# imu_sense.net
KiCad netlist of a schematic drawn in Altium Designer
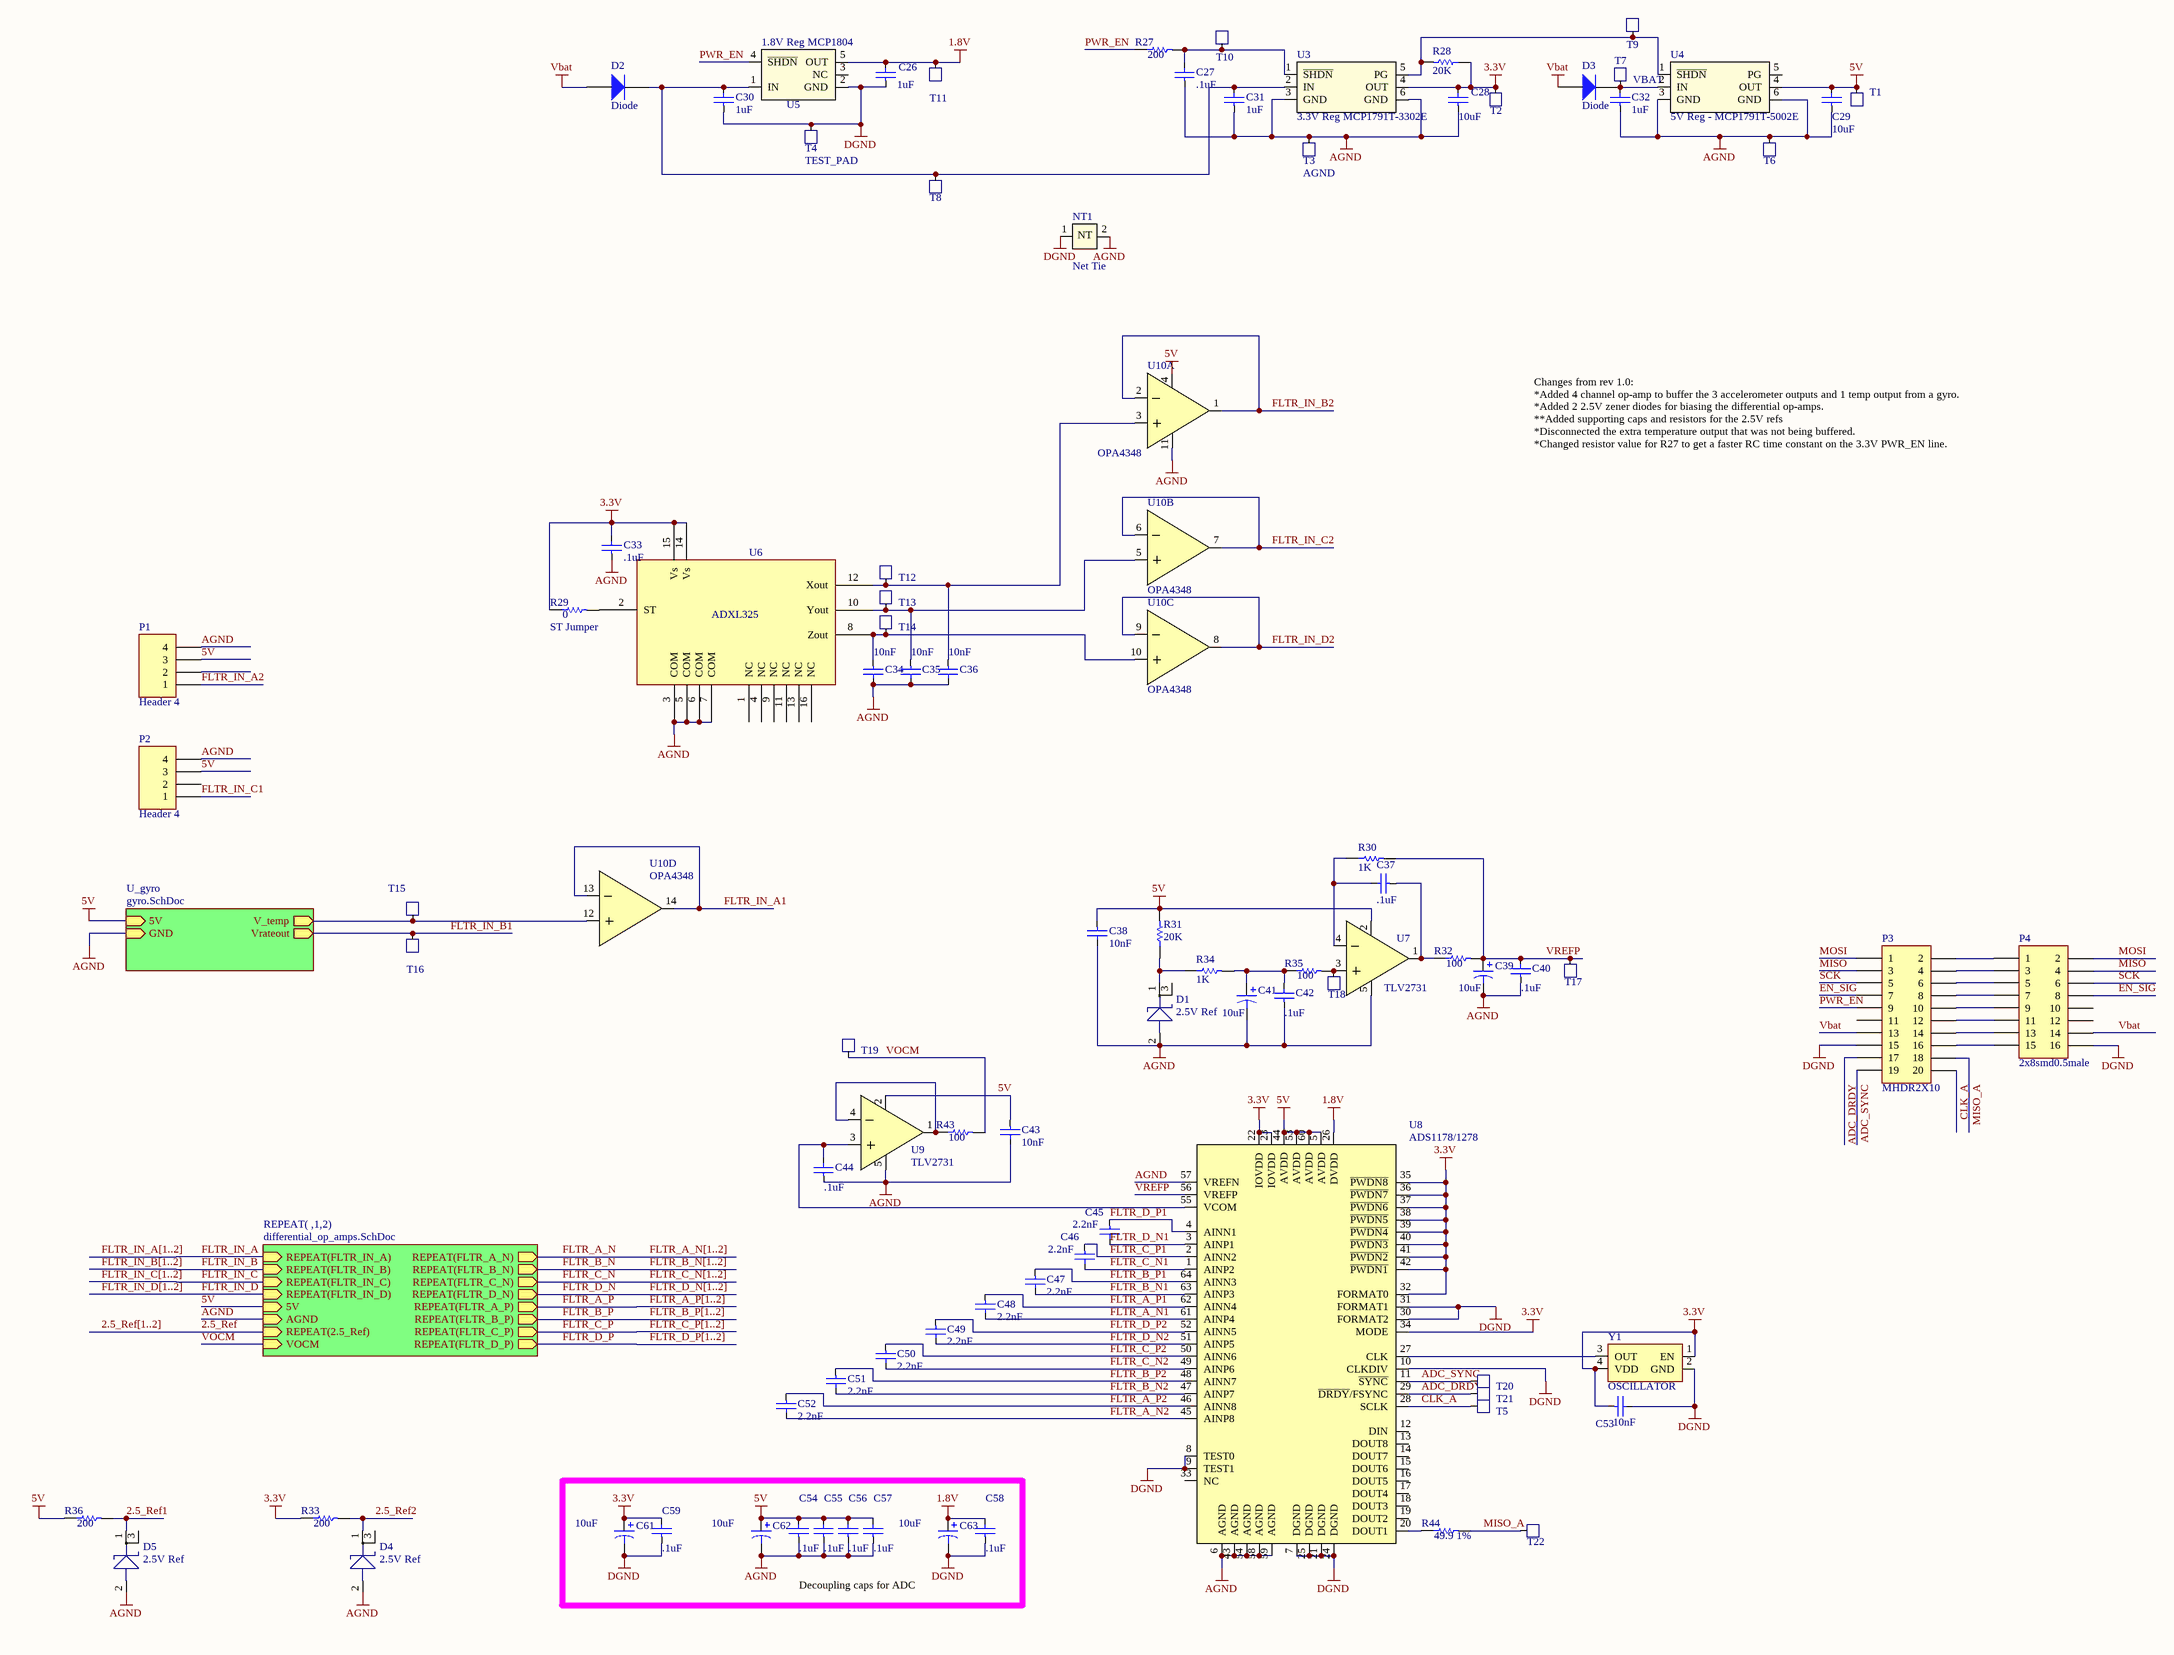
[diagram p0: imu_sense.SchDoc]

(export (version "E")
  (design (tool "Eeschema 10.0.6"))
  (components
    (comp (ref "C26")
      (value "1uF")
      (footprint "0603 (1608)")
      (fields
        (field (name "MANUFACTURER") "Murata")
        (field (name "PART NO.") "81-GRM188R61E105KA12")
        (field (name "TOLERANCE") "10%")
      )
      (libsource (lib "SMT Chip") (part "Capacitor"))
    )
    (comp (ref "C27")
      (value ".1uF")
      (footprint "0603 (1608)")
      (fields
        (field (name "MANUFACTURER") "Murata")
        (field (name "PART NO.") "490-1524-1-ND")
        (field (name "Comment") "Capacitor")
      )
      (libsource (lib "SMT Chip") (part "Capacitor"))
    )
    (comp (ref "C28")
      (value "10uF")
      (footprint "0603 (1608)")
      (fields
        (field (name "MANUFACTURER") "Murata")
        (field (name "PART NO.") "810-C1608X5R0J106K")
        (field (name "TOLERANCE") "10%")
      )
      (libsource (lib "SMT Chip") (part "Capacitor"))
    )
    (comp (ref "C29")
      (value "10uF")
      (footprint "0603 (1608)")
      (fields
        (field (name "MANUFACTURER") "Murata")
        (field (name "PART NO.") "810-C1608X5R0J106K")
        (field (name "TOLERANCE") "10%")
      )
      (libsource (lib "SMT Chip") (part "Capacitor"))
    )
    (comp (ref "C30")
      (value "1uF")
      (footprint "0603 (1608)")
      (fields
        (field (name "MANUFACTURER") "Murata")
        (field (name "PART NO.") "81-GRM188R61E105KA12")
        (field (name "TOLERANCE") "10%")
      )
      (libsource (lib "SMT Chip") (part "Capacitor"))
    )
    (comp (ref "C31")
      (value "1uF")
      (footprint "0603 (1608)")
      (fields
        (field (name "MANUFACTURER") "Murata")
        (field (name "PART NO.") "81-GRM188R61E105KA12")
        (field (name "TOLERANCE") "10%")
      )
      (libsource (lib "SMT Chip") (part "Capacitor"))
    )
    (comp (ref "C32")
      (value "1uF")
      (footprint "0603 (1608)")
      (fields
        (field (name "MANUFACTURER") "Murata")
        (field (name "PART NO.") "81-GRM188R61E105KA12")
        (field (name "TOLERANCE") "10%")
      )
      (libsource (lib "SMT Chip") (part "Capacitor"))
    )
    (comp (ref "C33")
      (value ".1uF")
      (footprint "0603 (1608)")
      (fields
        (field (name "MANUFACTURER") "Murata")
        (field (name "PART NO.") "490-1524-1-ND")
        (field (name "Comment") "Capacitor")
      )
      (libsource (lib "SMT Chip") (part "Capacitor"))
    )
    (comp (ref "C34")
      (value "10nF")
      (footprint "0603 (1608)")
      (fields
        (field (name "MANUFACTURER") "TDK")
        (field (name "PART NO.") "445-5099-1-ND")
        (field (name "TOLERANCE") "5%")
      )
      (libsource (lib "SMT Chip") (part "Capacitor"))
    )
    (comp (ref "C35")
      (value "10nF")
      (footprint "0603 (1608)")
      (fields
        (field (name "MANUFACTURER") "TDK")
        (field (name "PART NO.") "445-5099-1-ND")
        (field (name "TOLERANCE") "5%")
      )
      (libsource (lib "SMT Chip") (part "Capacitor"))
    )
    (comp (ref "C36")
      (value "10nF")
      (footprint "0603 (1608)")
      (fields
        (field (name "MANUFACTURER") "TDK")
        (field (name "PART NO.") "445-5099-1-ND")
        (field (name "TOLERANCE") "5%")
      )
      (libsource (lib "SMT Chip") (part "Capacitor"))
    )
    (comp (ref "C37")
      (value ".1uF")
      (footprint "0603 (1608)")
      (fields
        (field (name "MANUFACTURER") "Murata")
        (field (name "PART NO.") "490-1524-1-ND")
        (field (name "Comment") "Capacitor")
      )
      (libsource (lib "SMT Chip") (part "Capacitor"))
    )
    (comp (ref "C38")
      (value "10nF")
      (footprint "0603 (1608)")
      (fields
        (field (name "MANUFACTURER") "TDK")
        (field (name "PART NO.") "445-5099-1-ND")
        (field (name "TOLERANCE") "5%")
      )
      (libsource (lib "SMT Chip") (part "Capacitor"))
    )
    (comp (ref "C39")
      (value "10uF")
      (footprint "CAP-POL 0603(1608)")
      (description "Polarized Capacitor (Surface Mount)")
      (fields (field (name "PART NO.") "71-298D106X06R3M2T") (field (name "Comment") "tant"))
      (libsource (lib "Miscellaneous Devices") (part "Cap Pol3"))
    )
    (comp (ref "C40")
      (value ".1uF")
      (footprint "0603 (1608)")
      (fields
        (field (name "MANUFACTURER") "Murata")
        (field (name "PART NO.") "490-1524-1-ND")
        (field (name "Comment") "Capacitor")
      )
      (libsource (lib "SMT Chip") (part "Capacitor"))
    )
    (comp (ref "C41")
      (value "10uF")
      (footprint "CAP-POL 0603(1608)")
      (description "Polarized Capacitor (Surface Mount)")
      (fields (field (name "PART NO.") "71-298D106X06R3M2T") (field (name "Comment") "tant"))
      (libsource (lib "Miscellaneous Devices") (part "Cap Pol3"))
    )
    (comp (ref "C42")
      (value ".1uF")
      (footprint "0603 (1608)")
      (fields
        (field (name "MANUFACTURER") "Murata")
        (field (name "PART NO.") "490-1524-1-ND")
        (field (name "Comment") "Capacitor")
      )
      (libsource (lib "SMT Chip") (part "Capacitor"))
    )
    (comp (ref "C43")
      (value "10nF")
      (footprint "0603 (1608)")
      (fields
        (field (name "MANUFACTURER") "TDK")
        (field (name "PART NO.") "445-5099-1-ND")
        (field (name "TOLERANCE") "5%")
      )
      (libsource (lib "SMT Chip") (part "Capacitor"))
    )
    (comp (ref "C44")
      (value ".1uF")
      (footprint "0603 (1608)")
      (fields
        (field (name "MANUFACTURER") "Murata")
        (field (name "PART NO.") "490-1524-1-ND")
        (field (name "Comment") "Capacitor")
      )
      (libsource (lib "SMT Chip") (part "Capacitor"))
    )
    (comp (ref "C45")
      (value "2.2nF")
      (footprint "0603 (1608)")
      (description "COG Ceramic Cap -> near input to ads1178")
      (fields (field (name "MANUFACTURER") "Murata") (field (name "PART NO.") "490-1459-1-ND"))
      (libsource (lib "SMT Chip") (part "Capacitor"))
    )
    (comp (ref "C46")
      (value "2.2nF")
      (footprint "0603 (1608)")
      (description "COG Ceramic Cap -> near input to ads1178")
      (fields (field (name "MANUFACTURER") "Murata") (field (name "PART NO.") "490-1459-1-ND"))
      (libsource (lib "SMT Chip") (part "Capacitor"))
    )
    (comp (ref "C47")
      (value "2.2nF")
      (footprint "0603 (1608)")
      (description "COG Ceramic Cap -> near input to ads1178")
      (fields (field (name "MANUFACTURER") "Murata") (field (name "PART NO.") "490-1459-1-ND"))
      (libsource (lib "SMT Chip") (part "Capacitor"))
    )
    (comp (ref "C48")
      (value "2.2nF")
      (footprint "0603 (1608)")
      (description "COG Ceramic Cap -> near input to ads1178")
      (fields (field (name "MANUFACTURER") "Murata") (field (name "PART NO.") "490-1459-1-ND"))
      (libsource (lib "SMT Chip") (part "Capacitor"))
    )
    (comp (ref "C49")
      (value "2.2nF")
      (footprint "0603 (1608)")
      (description "COG Ceramic Cap -> near input to ads1178")
      (fields (field (name "MANUFACTURER") "Murata") (field (name "PART NO.") "490-1459-1-ND"))
      (libsource (lib "SMT Chip") (part "Capacitor"))
    )
    (comp (ref "C50")
      (value "2.2nF")
      (footprint "0603 (1608)")
      (description "COG Ceramic Cap -> near input to ads1178")
      (fields (field (name "MANUFACTURER") "Murata") (field (name "PART NO.") "490-1459-1-ND"))
      (libsource (lib "SMT Chip") (part "Capacitor"))
    )
    (comp (ref "C51")
      (value "2.2nF")
      (footprint "0603 (1608)")
      (description "COG Ceramic Cap -> near input to ads1178")
      (fields (field (name "MANUFACTURER") "Murata") (field (name "PART NO.") "490-1459-1-ND"))
      (libsource (lib "SMT Chip") (part "Capacitor"))
    )
    (comp (ref "C52")
      (value "2.2nF")
      (footprint "0603 (1608)")
      (description "COG Ceramic Cap -> near input to ads1178")
      (fields (field (name "MANUFACTURER") "Murata") (field (name "PART NO.") "490-1459-1-ND"))
      (libsource (lib "SMT Chip") (part "Capacitor"))
    )
    (comp (ref "C53")
      (value "10nF")
      (footprint "0603 (1608)")
      (fields
        (field (name "MANUFACTURER") "TDK")
        (field (name "PART NO.") "445-5099-1-ND")
        (field (name "TOLERANCE") "5%")
      )
      (libsource (lib "SMT Chip") (part "Capacitor"))
    )
    (comp (ref "C54")
      (value ".1uF")
      (footprint "0603 (1608)")
      (fields
        (field (name "MANUFACTURER") "Murata")
        (field (name "PART NO.") "490-1524-1-ND")
        (field (name "Comment") "Capacitor")
      )
      (libsource (lib "SMT Chip") (part "Capacitor"))
    )
    (comp (ref "C55")
      (value ".1uF")
      (footprint "0603 (1608)")
      (fields
        (field (name "MANUFACTURER") "Murata")
        (field (name "PART NO.") "490-1524-1-ND")
        (field (name "Comment") "Capacitor")
      )
      (libsource (lib "SMT Chip") (part "Capacitor"))
    )
    (comp (ref "C56")
      (value ".1uF")
      (footprint "0603 (1608)")
      (fields
        (field (name "MANUFACTURER") "Murata")
        (field (name "PART NO.") "490-1524-1-ND")
        (field (name "Comment") "Capacitor")
      )
      (libsource (lib "SMT Chip") (part "Capacitor"))
    )
    (comp (ref "C57")
      (value ".1uF")
      (footprint "0603 (1608)")
      (fields
        (field (name "MANUFACTURER") "Murata")
        (field (name "PART NO.") "490-1524-1-ND")
        (field (name "Comment") "Capacitor")
      )
      (libsource (lib "SMT Chip") (part "Capacitor"))
    )
    (comp (ref "C58")
      (value ".1uF")
      (footprint "0603 (1608)")
      (fields
        (field (name "MANUFACTURER") "Murata")
        (field (name "PART NO.") "490-1524-1-ND")
        (field (name "Comment") "Capacitor")
      )
      (libsource (lib "SMT Chip") (part "Capacitor"))
    )
    (comp (ref "C59")
      (value ".1uF")
      (footprint "0603 (1608)")
      (fields
        (field (name "MANUFACTURER") "Murata")
        (field (name "PART NO.") "490-1524-1-ND")
        (field (name "Comment") "Capacitor")
      )
      (libsource (lib "SMT Chip") (part "Capacitor"))
    )
    (comp (ref "C61")
      (value "10uF")
      (footprint "CAP-POL 0603(1608)")
      (description "Polarized Capacitor (Surface Mount)")
      (fields (field (name "PART NO.") "71-298D106X06R3M2T") (field (name "Comment") "tant"))
      (libsource (lib "Miscellaneous Devices") (part "Cap Pol3"))
    )
    (comp (ref "C62")
      (value "10uF")
      (footprint "CAP-POL 0603(1608)")
      (description "Polarized Capacitor (Surface Mount)")
      (fields (field (name "PART NO.") "71-298D106X06R3M2T") (field (name "Comment") "tant"))
      (libsource (lib "Miscellaneous Devices") (part "Cap Pol3"))
    )
    (comp (ref "C63")
      (value "10uF")
      (footprint "CAP-POL 0603(1608)")
      (description "Polarized Capacitor (Surface Mount)")
      (fields (field (name "PART NO.") "71-298D106X06R3M2T") (field (name "Comment") "tant"))
      (libsource (lib "Miscellaneous Devices") (part "Cap Pol3"))
    )
    (comp (ref "D1")
      (value "2.5V Ref")
      (footprint "SC-70")
      (description "2.5 volt ref")
      (fields
        (field (name "PART NO.") "ADR525BKSZ-REEL7CT-ND")
        (field (name "MANUFACTURER") "Analog Devices")
      )
      (libsource (lib "imu") (part "ZENER"))
    )
    (comp (ref "D2")
      (value "Diode")
      (footprint "0603(1608) diode - line on pin2")
      (description "Reverse voltage protection diode")
      (fields (field (name "PART NO.") "641-1332-1-ND"))
      (libsource (lib "Miscellaneous Devices") (part "Diode"))
    )
    (comp (ref "D3")
      (value "Diode")
      (footprint "0603(1608) diode - line on pin2")
      (description "Reverse voltage protection diode")
      (fields (field (name "PART NO.") "641-1332-1-ND"))
      (libsource (lib "Miscellaneous Devices") (part "Diode"))
    )
    (comp (ref "D4")
      (value "2.5V Ref")
      (footprint "SC-70")
      (description "2.5 volt ref")
      (fields
        (field (name "PART NO.") "ADR525BKSZ-REEL7CT-ND")
        (field (name "MANUFACTURER") "Analog Devices")
      )
      (libsource (lib "imu") (part "ZENER"))
    )
    (comp (ref "D5")
      (value "2.5V Ref")
      (footprint "SC-70")
      (description "2.5 volt ref")
      (fields
        (field (name "PART NO.") "ADR525BKSZ-REEL7CT-ND")
        (field (name "MANUFACTURER") "Analog Devices")
      )
      (libsource (lib "imu") (part "ZENER"))
    )
    (comp (ref "NT1") (value "Net Tie") (footprint "NET_TIE") (libsource (lib "imu") (part "NET_TIE")))
    (comp (ref "P1")
      (value "Header 4")
      (footprint "gyro mount")
      (description "Header, 4-Pin")
      (fields (field (name "PART NO.") "A31114-ND"))
      (libsource (lib "Miscellaneous Connectors") (part "Header 4"))
    )
    (comp (ref "P2")
      (value "Header 4")
      (footprint "gyro mount")
      (description "Header, 4-Pin")
      (fields (field (name "PART NO.") "A31114-ND"))
      (libsource (lib "Miscellaneous Connectors") (part "Header 4"))
    )
    (comp (ref "P3")
      (value "MHDR2X10")
      (footprint "S9013E-10-ND")
      (description "Header, 10-Pin, Female")
      (fields (field (name "PART NO.") "S9007E-10-ND"))
      (libsource (lib "Miscellaneous Connectors") (part "MHDR2X10"))
    )
    (comp (ref "P4")
      (value "2x8smd0.5male")
      (footprint "Header, right hole")
      (fields (field (name "PART NO.") "S9013E-08-ND"))
      (libsource (lib "falcon") (part "2x8smd0.5male"))
    )
    (comp (ref "R27")
      (value "200")
      (footprint "0603 (1608)")
      (description "Resistor")
      (fields (field (name "PART NO.") "P200GCT-ND"))
      (libsource (lib "Miscellaneous Devices") (part "Res1"))
    )
    (comp (ref "R28")
      (value "20K")
      (footprint "0603 (1608)")
      (description "Resistor")
      (fields (field (name "PART NO.") "P20KGCT-ND"))
      (libsource (lib "Miscellaneous Devices") (part "Res1"))
    )
    (comp (ref "R29")
      (value "ST Jumper")
      (footprint "0603 (1608)")
      (description "Resistor")
      (fields (field (name "ALTIUM_VALUE") "0") (field (name "PART NO.") "P0.0GCT-ND"))
      (libsource (lib "Miscellaneous Devices") (part "Res1"))
    )
    (comp (ref "R30")
      (value "1K")
      (footprint "0603 (1608)")
      (description "Resistor")
      (fields (field (name "PART NO.") "P1.0KGCT-ND") (field (name "TOLERANCE") "5%"))
      (libsource (lib "Miscellaneous Devices") (part "Res1"))
    )
    (comp (ref "R31")
      (value "20K")
      (footprint "0603 (1608)")
      (description "Resistor")
      (fields (field (name "PART NO.") "P20KGCT-ND"))
      (libsource (lib "Miscellaneous Devices") (part "Res1"))
    )
    (comp (ref "R32")
      (value "100")
      (footprint "0603 (1608)")
      (description "Resistor")
      (fields (field (name "PART NO.") "P100GCT-ND"))
      (libsource (lib "Miscellaneous Devices") (part "Res1"))
    )
    (comp (ref "R33")
      (value "200")
      (footprint "0603 (1608)")
      (description "Resistor")
      (fields (field (name "PART NO.") "P200GCT-ND"))
      (libsource (lib "Miscellaneous Devices") (part "Res1"))
    )
    (comp (ref "R34")
      (value "1K")
      (footprint "0603 (1608)")
      (description "Resistor")
      (fields (field (name "PART NO.") "P1.0KGCT-ND") (field (name "TOLERANCE") "5%"))
      (libsource (lib "Miscellaneous Devices") (part "Res1"))
    )
    (comp (ref "R35")
      (value "100")
      (footprint "0603 (1608)")
      (description "Resistor")
      (fields (field (name "PART NO.") "P100GCT-ND"))
      (libsource (lib "Miscellaneous Devices") (part "Res1"))
    )
    (comp (ref "R36")
      (value "200")
      (footprint "0603 (1608)")
      (description "Resistor")
      (fields (field (name "PART NO.") "P200GCT-ND"))
      (libsource (lib "Miscellaneous Devices") (part "Res1"))
    )
    (comp (ref "R43")
      (value "100")
      (footprint "0603 (1608)")
      (description "Resistor")
      (fields (field (name "PART NO.") "P100GCT-ND"))
      (libsource (lib "Miscellaneous Devices") (part "Res1"))
    )
    (comp (ref "R44")
      (value "49.9 1%")
      (footprint "0603 (1608)")
      (description "Resistor")
      (fields (field (name "PART NO.") "P49.9HCT-ND") (field (name "Comment") "931 1%"))
      (libsource (lib "Miscellaneous Devices") (part "Res1"))
    )
    (comp (ref "T1") (value "TEST_PAD") (footprint "TEST_PAD") (libsource (lib "imu") (part "TEST_PAD")))
    (comp (ref "T2") (value "TEST_PAD") (footprint "TEST_PAD") (libsource (lib "imu") (part "TEST_PAD")))
    (comp (ref "T3") (value "AGND") (footprint "TEST_PAD") (libsource (lib "imu") (part "TEST_PAD")))
    (comp (ref "T4") (value "TEST_PAD") (footprint "TEST_PAD") (libsource (lib "imu") (part "TEST_PAD")))
    (comp (ref "T5") (value "TEST_PAD") (footprint "TEST_PAD") (libsource (lib "") (part "TEST_PAD_2")))
    (comp (ref "T6") (value "TEST_PAD") (footprint "TEST_PAD") (libsource (lib "imu") (part "TEST_PAD")))
    (comp (ref "T7") (value "VBAT") (footprint "TEST_PAD") (libsource (lib "") (part "TEST_PAD_1")))
    (comp (ref "T8") (value "TEST_PAD") (footprint "TEST_PAD") (libsource (lib "imu") (part "TEST_PAD")))
    (comp (ref "T9") (value "TEST_PAD") (footprint "TEST_PAD") (libsource (lib "") (part "TEST_PAD_1")))
    (comp (ref "T10") (value "TEST_PAD") (footprint "TEST_PAD") (libsource (lib "") (part "TEST_PAD_1")))
    (comp (ref "T11") (value "TEST_PAD") (footprint "TEST_PAD") (libsource (lib "imu") (part "TEST_PAD")))
    (comp (ref "T12") (value "~") (footprint "TEST_PAD") (libsource (lib "") (part "TEST_PAD_1")))
    (comp (ref "T13") (value "~") (footprint "TEST_PAD") (libsource (lib "") (part "TEST_PAD_1")))
    (comp (ref "T14") (value "~") (footprint "TEST_PAD") (libsource (lib "") (part "TEST_PAD_1")))
    (comp (ref "T15") (value "~") (footprint "TEST_PAD") (libsource (lib "") (part "TEST_PAD_1")))
    (comp (ref "T16") (value "~") (footprint "TEST_PAD") (libsource (lib "imu") (part "TEST_PAD")))
    (comp (ref "T17") (value "~") (footprint "TEST_PAD") (libsource (lib "imu") (part "TEST_PAD")))
    (comp (ref "T18") (value "~") (footprint "TEST_PAD") (libsource (lib "imu") (part "TEST_PAD")))
    (comp (ref "T19") (value "~") (footprint "TEST_PAD") (libsource (lib "") (part "TEST_PAD_1")))
    (comp (ref "T20") (value "~") (footprint "TEST_PAD") (libsource (lib "") (part "TEST_PAD_2")))
    (comp (ref "T21") (value "~") (footprint "TEST_PAD") (libsource (lib "") (part "TEST_PAD_2")))
    (comp (ref "T22") (value "TEST_PAD") (footprint "TEST_PAD") (libsource (lib "") (part "TEST_PAD_2")))
    (comp (ref "U3")
      (value "3.3V Reg MCP1791T-3302E")
      (footprint "SOT223 - 5 leads + tab")
      (description "3.3V, 70mA LDO with SHDN and PWRGD pins")
      (fields (field (name "PART NO.") "MCP1791T-3302E/DCCT-ND"))
      (libsource (lib "imu") (part "5V Reg - MCP1791T-5002E/DC"))
    )
    (comp (ref "U4")
      (value "5V Reg - MCP1791T-5002E")
      (footprint "SOT223 - 5 leads + tab")
      (description "5V, 70mA LDO with SHDN and PWRGD pins")
      (fields (field (name "PART NO.") "MCP1791T-5002E/DCCT-ND"))
      (libsource (lib "imu") (part "5V Reg - MCP1791T-5002E/DC"))
    )
    (comp (ref "U5")
      (value "1.8V Reg MCP1804")
      (footprint "SOT23-5 - MCP1804T")
      (description "1.8V Reg. MCP1804")
      (fields (field (name "PART NO.") "MCP1804T-1802I/OTCT-ND"))
      (libsource (lib "imu") (part "1.8V Reg"))
    )
    (comp (ref "U6")
      (value "ADXL325")
      (footprint "LFCSP_LQ_AXDL")
      (fields (field (name "PART NO.") "ADXL325BCPZ-RL7CT-ND"))
      (libsource (lib "imu") (part "ADXL325"))
    )
    (comp (ref "U7")
      (value "TLV2731")
      (footprint "SOT23-5 Ti Op Amp")
      (fields (field (name "PART NO.") "296-10656-1-ND") (field (name "MANUFACTURER") "Texas Instruments"))
      (libsource (lib "imu") (part "TI Small Op Amp"))
    )
    (comp (ref "U8")
      (value "ADS1178/1278")
      (footprint "S-PQFP-G64")
      (description "The ADS1178 and 1278 are pin compatible. 16 and 24 bits, respectively.")
      (fields (field (name "MANUFACTURER") "Texas Instruments"))
      (libsource (lib "imu") (part "ADS1178"))
    )
    (comp (ref "U9")
      (value "TLV2731")
      (footprint "SOT23-5 Ti Op Amp")
      (fields (field (name "PART NO.") "296-10656-1-ND") (field (name "MANUFACTURER") "Texas Instruments"))
      (libsource (lib "imu") (part "TI Small Op Amp"))
    )
    (comp (ref "U10")
      (value "OPA4348")
      (footprint "TSSOP-14")
      (fields (field (name "PART NO.") "296-12277-5-ND"))
      (libsource (lib "imu") (part "OPA4348"))
    )
    (comp (ref "Y1")
      (value "OSCILLATOR")
      (footprint "ABRACON Oscillator")
      (fields (field (name "PART NO.") "535-9778-1-ND") (field (name "MANUFACTURER") "Abracon"))
      (libsource (lib "imu") (part "OSCILLATOR"))
    )
  )
  (nets
    (net (code "3") (name "/2.5_Ref1") (class "Default")
      (node (ref "D5") (pin "1") (pinfunction "Cathode_1") (pintype "passive"))
      (node (ref "R36") (pin "2") (pinfunction "2_2") (pintype "passive"))
    )
    (net (code "4") (name "/2.5_Ref2") (class "Default")
      (node (ref "D4") (pin "1") (pinfunction "Cathode_1") (pintype "passive"))
      (node (ref "R33") (pin "2") (pinfunction "2_2") (pintype "passive"))
    )
    (net (code "6") (name "/ADC_DRDY") (class "Default")
      (node (ref "P3") (pin "17") (pinfunction "17_17") (pintype "passive"))
      (node (ref "T21") (pin "0") (pintype "passive"))
      (node (ref "U8") (pin "29") (pinfunction "~{DRDY}/FSYNC_29") (pintype "passive"))
    )
    (net (code "7") (name "/ADC_SYNC") (class "Default")
      (node (ref "P3") (pin "19") (pinfunction "19_19") (pintype "passive"))
      (node (ref "T20") (pin "0") (pintype "passive"))
      (node (ref "U8") (pin "11") (pinfunction "~{SYNC}_11") (pintype "passive"))
    )
    (net (code "8") (name "/CLK_A") (class "Default")
      (node (ref "P3") (pin "20") (pinfunction "20_20") (pintype "passive"))
      (node (ref "T5") (pin "0") (pintype "passive"))
      (node (ref "U8") (pin "28") (pinfunction "SCLK_28") (pintype "passive"))
    )
    (net (code "9") (name "/EN_SIG") (class "Default")
      (node (ref "P3") (pin "7") (pinfunction "7_7") (pintype "passive"))
      (node (ref "P4") (pin "8") (pinfunction "8_8") (pintype "passive"))
    )
    (net (code "11") (name "/FLTR_A_N1") (class "Default")
      (node (ref "C48") (pin "1") (pinfunction "1_1") (pintype "passive"))
      (node (ref "U8") (pin "61") (pinfunction "AINP4_61") (pintype "passive"))
    )
    (net (code "12") (name "/FLTR_A_N2") (class "Default")
      (node (ref "C52") (pin "1") (pinfunction "1_1") (pintype "passive"))
      (node (ref "U8") (pin "45") (pinfunction "AINP8_45") (pintype "passive"))
    )
    (net (code "15") (name "/FLTR_A_P1") (class "Default")
      (node (ref "C48") (pin "2") (pinfunction "2_2") (pintype "passive"))
      (node (ref "U8") (pin "62") (pinfunction "AINN4_62") (pintype "passive"))
    )
    (net (code "16") (name "/FLTR_A_P2") (class "Default")
      (node (ref "C52") (pin "2") (pinfunction "2_2") (pintype "passive"))
      (node (ref "U8") (pin "46") (pinfunction "AINN8_46") (pintype "passive"))
    )
    (net (code "19") (name "/FLTR_B_N1") (class "Default")
      (node (ref "C47") (pin "1") (pinfunction "1_1") (pintype "passive"))
      (node (ref "U8") (pin "63") (pinfunction "AINP3_63") (pintype "passive"))
    )
    (net (code "20") (name "/FLTR_B_N2") (class "Default")
      (node (ref "C51") (pin "1") (pinfunction "1_1") (pintype "passive"))
      (node (ref "U8") (pin "47") (pinfunction "AINP7_47") (pintype "passive"))
    )
    (net (code "23") (name "/FLTR_B_P1") (class "Default")
      (node (ref "C47") (pin "2") (pinfunction "2_2") (pintype "passive"))
      (node (ref "U8") (pin "64") (pinfunction "AINN3_64") (pintype "passive"))
    )
    (net (code "24") (name "/FLTR_B_P2") (class "Default")
      (node (ref "C51") (pin "2") (pinfunction "2_2") (pintype "passive"))
      (node (ref "U8") (pin "48") (pinfunction "AINN7_48") (pintype "passive"))
    )
    (net (code "27") (name "/FLTR_C_N1") (class "Default")
      (node (ref "C46") (pin "1") (pinfunction "1_1") (pintype "passive"))
      (node (ref "U8") (pin "1") (pinfunction "AINP2_1") (pintype "passive"))
    )
    (net (code "28") (name "/FLTR_C_N2") (class "Default")
      (node (ref "C50") (pin "1") (pinfunction "1_1") (pintype "passive"))
      (node (ref "U8") (pin "49") (pinfunction "AINP6_49") (pintype "passive"))
    )
    (net (code "31") (name "/FLTR_C_P1") (class "Default")
      (node (ref "C46") (pin "2") (pinfunction "2_2") (pintype "passive"))
      (node (ref "U8") (pin "2") (pinfunction "AINN2_2") (pintype "passive"))
    )
    (net (code "32") (name "/FLTR_C_P2") (class "Default")
      (node (ref "C50") (pin "2") (pinfunction "2_2") (pintype "passive"))
      (node (ref "U8") (pin "50") (pinfunction "AINN6_50") (pintype "passive"))
    )
    (net (code "35") (name "/FLTR_D_N1") (class "Default")
      (node (ref "C45") (pin "1") (pinfunction "1_1") (pintype "passive"))
      (node (ref "U8") (pin "3") (pinfunction "AINP1_3") (pintype "passive"))
    )
    (net (code "36") (name "/FLTR_D_N2") (class "Default")
      (node (ref "C49") (pin "1") (pinfunction "1_1") (pintype "passive"))
      (node (ref "U8") (pin "51") (pinfunction "AINP5_51") (pintype "passive"))
    )
    (net (code "39") (name "/FLTR_D_P1") (class "Default")
      (node (ref "C45") (pin "2") (pinfunction "2_2") (pintype "passive"))
      (node (ref "U8") (pin "4") (pinfunction "AINN1_4") (pintype "passive"))
    )
    (net (code "40") (name "/FLTR_D_P2") (class "Default")
      (node (ref "C49") (pin "2") (pinfunction "2_2") (pintype "passive"))
      (node (ref "U8") (pin "52") (pinfunction "AINN5_52") (pintype "passive"))
    )
    (net (code "43") (name "/FLTR_IN_A1") (class "Default")
      (node (ref "U10") (pin "13") (pinfunction "-IN_13") (pintype "passive"))
      (node (ref "U10") (pin "14") (pinfunction "Out_14") (pintype "passive"))
    )
    (net (code "44") (name "/FLTR_IN_A2") (class "Default")
      (node (ref "P1") (pin "1") (pinfunction "1_1") (pintype "passive"))
    )
    (net (code "47") (name "/FLTR_IN_B1") (class "Default") (node (ref "T16") (pin "0") (pintype "passive")))
    (net (code "48") (name "/FLTR_IN_B2") (class "Default")
      (node (ref "U10") (pin "1") (pinfunction "Out_1") (pintype "passive"))
      (node (ref "U10") (pin "2") (pinfunction "-IN_2") (pintype "passive"))
    )
    (net (code "51") (name "/FLTR_IN_C1") (class "Default")
      (node (ref "P2") (pin "1") (pinfunction "1_1") (pintype "passive"))
    )
    (net (code "52") (name "/FLTR_IN_C2") (class "Default")
      (node (ref "U10") (pin "6") (pinfunction "-IN_6") (pintype "passive"))
      (node (ref "U10") (pin "7") (pinfunction "Out_7") (pintype "passive"))
    )
    (net (code "55") (name "/FLTR_IN_D2") (class "Default")
      (node (ref "U10") (pin "8") (pinfunction "Out_8") (pintype "passive"))
      (node (ref "U10") (pin "9") (pinfunction "-IN_9") (pintype "passive"))
    )
    (net (code "57") (name "/MISO") (class "Default")
      (node (ref "P3") (pin "3") (pinfunction "3_3") (pintype "passive"))
      (node (ref "P4") (pin "4") (pinfunction "4_4") (pintype "passive"))
    )
    (net (code "58") (name "/MISO_A") (class "Default")
      (node (ref "P3") (pin "18") (pinfunction "18_18") (pintype "passive"))
      (node (ref "R44") (pin "2") (pinfunction "2_2") (pintype "passive"))
      (node (ref "T22") (pin "0") (pintype "passive"))
    )
    (net (code "59") (name "/MOSI") (class "Default")
      (node (ref "P3") (pin "1") (pinfunction "1_1") (pintype "passive"))
      (node (ref "P4") (pin "2") (pinfunction "2_2") (pintype "passive"))
    )
    (net (code "60") (name "/PWR_EN") (class "Default")
      (node (ref "P3") (pin "9") (pinfunction "9_9") (pintype "passive"))
      (node (ref "R27") (pin "1") (pinfunction "1_1") (pintype "passive"))
      (node (ref "U5") (pin "4") (pinfunction "~{SHDN}_4") (pintype "passive"))
    )
    (net (code "61") (name "/SCK") (class "Default")
      (node (ref "P3") (pin "5") (pinfunction "5_5") (pintype "passive"))
      (node (ref "P4") (pin "6") (pinfunction "6_6") (pintype "passive"))
    )
    (net (code "62") (name "/VOCM") (class "Default")
      (node (ref "R43") (pin "2") (pinfunction "2_2") (pintype "passive"))
      (node (ref "T19") (pin "0") (pintype "passive"))
    )
    (net (code "63") (name "/VREFP") (class "Default")
      (node (ref "C39") (pin "1") (pinfunction "1_1") (pintype "passive"))
      (node (ref "C40") (pin "1") (pinfunction "1_1") (pintype "passive"))
      (node (ref "R30") (pin "2") (pinfunction "2_2") (pintype "passive"))
      (node (ref "R32") (pin "2") (pinfunction "2_2") (pintype "passive"))
      (node (ref "T17") (pin "0") (pintype "passive"))
      (node (ref "U8") (pin "56") (pinfunction "VREFP_56") (pintype "passive"))
    )
    (net (code "64") (name "/V_temp") (class "Default")
      (node (ref "T15") (pin "0") (pintype "passive"))
      (node (ref "U10") (pin "12") (pinfunction "+IN_12") (pintype "passive"))
    )
    (net (code "65") (name "1.8V") (class "Default")
      (node (ref "C26") (pin "1") (pinfunction "1_1") (pintype "passive"))
      (node (ref "C58") (pin "1") (pinfunction "1_1") (pintype "passive"))
      (node (ref "C63") (pin "1") (pinfunction "1_1") (pintype "passive"))
      (node (ref "T11") (pin "0") (pintype "passive"))
      (node (ref "U5") (pin "5") (pinfunction "OUT_5") (pintype "passive"))
      (node (ref "U8") (pin "26") (pinfunction "DVDD_26") (pintype "passive"))
    )
    (net (code "66") (name "3.3V") (class "Default")
      (node (ref "C28") (pin "1") (pinfunction "1_1") (pintype "passive"))
      (node (ref "C33") (pin "1") (pinfunction "1_1") (pintype "passive"))
      (node (ref "C53") (pin "2") (pinfunction "2_2") (pintype "passive"))
      (node (ref "C59") (pin "1") (pinfunction "1_1") (pintype "passive"))
      (node (ref "C61") (pin "1") (pinfunction "1_1") (pintype "passive"))
      (node (ref "R28") (pin "1") (pinfunction "1_1") (pintype "passive"))
      (node (ref "R29") (pin "1") (pinfunction "1_1") (pintype "passive"))
      (node (ref "R33") (pin "1") (pinfunction "1_1") (pintype "passive"))
      (node (ref "T2") (pin "0") (pintype "passive"))
      (node (ref "U3") (pin "4") (pinfunction "OUT_4") (pintype "passive"))
      (node (ref "U6") (pin "14") (pinfunction "Vs_14") (pintype "passive"))
      (node (ref "U6") (pin "15") (pinfunction "Vs_15") (pintype "passive"))
      (node (ref "U8") (pin "22") (pinfunction "IOVDD_22") (pintype "passive"))
      (node (ref "U8") (pin "23") (pinfunction "IOVDD_23") (pintype "passive"))
      (node (ref "U8") (pin "32") (pinfunction "FORMAT0_32") (pintype "passive"))
      (node (ref "U8") (pin "34") (pinfunction "MODE_34") (pintype "passive"))
      (node (ref "U8") (pin "35") (pinfunction "~{PWDN8}_35") (pintype "passive"))
      (node (ref "U8") (pin "36") (pinfunction "~{PWDN7}_36") (pintype "passive"))
      (node (ref "U8") (pin "37") (pinfunction "~{PWDN6}_37") (pintype "passive"))
      (node (ref "U8") (pin "38") (pinfunction "~{PWDN5}_38") (pintype "passive"))
      (node (ref "U8") (pin "39") (pinfunction "~{PWDN4}_39") (pintype "passive"))
      (node (ref "U8") (pin "40") (pinfunction "~{PWDN3}_40") (pintype "passive"))
      (node (ref "U8") (pin "41") (pinfunction "~{PWDN2}_41") (pintype "passive"))
      (node (ref "U8") (pin "42") (pinfunction "~{PWDN1}_42") (pintype "passive"))
      (node (ref "Y1") (pin "1") (pinfunction "EN_1") (pintype "passive"))
      (node (ref "Y1") (pin "4") (pinfunction "VDD_4") (pintype "passive"))
    )
    (net (code "67") (name "5V") (class "Default")
      (node (ref "C29") (pin "1") (pinfunction "1_1") (pintype "passive"))
      (node (ref "C38") (pin "2") (pinfunction "2_2") (pintype "passive"))
      (node (ref "C43") (pin "2") (pinfunction "2_2") (pintype "passive"))
      (node (ref "C54") (pin "1") (pinfunction "1_1") (pintype "passive"))
      (node (ref "C55") (pin "1") (pinfunction "1_1") (pintype "passive"))
      (node (ref "C56") (pin "1") (pinfunction "1_1") (pintype "passive"))
      (node (ref "C57") (pin "1") (pinfunction "1_1") (pintype "passive"))
      (node (ref "C62") (pin "1") (pinfunction "1_1") (pintype "passive"))
      (node (ref "P1") (pin "3") (pinfunction "3_3") (pintype "passive"))
      (node (ref "P2") (pin "3") (pinfunction "3_3") (pintype "passive"))
      (node (ref "R31") (pin "2") (pinfunction "2_2") (pintype "passive"))
      (node (ref "R36") (pin "1") (pinfunction "1_1") (pintype "passive"))
      (node (ref "T1") (pin "0") (pintype "passive"))
      (node (ref "U10") (pin "4") (pinfunction "V+_4") (pintype "passive"))
      (node (ref "U4") (pin "4") (pinfunction "OUT_4") (pintype "passive"))
      (node (ref "U7") (pin "2") (pinfunction "V+_2") (pintype "passive"))
      (node (ref "U8") (pin "44") (pinfunction "AVDD_44") (pintype "passive"))
      (node (ref "U8") (pin "5") (pinfunction "AVDD_5") (pintype "passive"))
      (node (ref "U8") (pin "53") (pinfunction "AVDD_53") (pintype "passive"))
      (node (ref "U8") (pin "60") (pinfunction "AVDD_60") (pintype "passive"))
      (node (ref "U9") (pin "2") (pinfunction "V+_2") (pintype "passive"))
    )
    (net (code "68") (name "AGND") (class "Default")
      (node (ref "C27") (pin "2") (pinfunction "2_2") (pintype "passive"))
      (node (ref "C28") (pin "2") (pinfunction "2_2") (pintype "passive"))
      (node (ref "C29") (pin "2") (pinfunction "2_2") (pintype "passive"))
      (node (ref "C31") (pin "2") (pinfunction "2_2") (pintype "passive"))
      (node (ref "C32") (pin "2") (pinfunction "2_2") (pintype "passive"))
      (node (ref "C33") (pin "2") (pinfunction "2_2") (pintype "passive"))
      (node (ref "C34") (pin "1") (pinfunction "1_1") (pintype "passive"))
      (node (ref "C35") (pin "1") (pinfunction "1_1") (pintype "passive"))
      (node (ref "C36") (pin "1") (pinfunction "1_1") (pintype "passive"))
      (node (ref "C38") (pin "1") (pinfunction "1_1") (pintype "passive"))
      (node (ref "C39") (pin "2") (pinfunction "2_2") (pintype "passive"))
      (node (ref "C40") (pin "2") (pinfunction "2_2") (pintype "passive"))
      (node (ref "C41") (pin "2") (pinfunction "2_2") (pintype "passive"))
      (node (ref "C42") (pin "2") (pinfunction "2_2") (pintype "passive"))
      (node (ref "C43") (pin "1") (pinfunction "1_1") (pintype "passive"))
      (node (ref "C44") (pin "2") (pinfunction "2_2") (pintype "passive"))
      (node (ref "C54") (pin "2") (pinfunction "2_2") (pintype "passive"))
      (node (ref "C55") (pin "2") (pinfunction "2_2") (pintype "passive"))
      (node (ref "C56") (pin "2") (pinfunction "2_2") (pintype "passive"))
      (node (ref "C57") (pin "2") (pinfunction "2_2") (pintype "passive"))
      (node (ref "C62") (pin "2") (pinfunction "2_2") (pintype "passive"))
      (node (ref "D1") (pin "2") (pinfunction "Anode_2") (pintype "passive"))
      (node (ref "D4") (pin "2") (pinfunction "Anode_2") (pintype "passive"))
      (node (ref "D5") (pin "2") (pinfunction "Anode_2") (pintype "passive"))
      (node (ref "NT1") (pin "2") (pintype "passive"))
      (node (ref "P1") (pin "4") (pinfunction "4_4") (pintype "passive"))
      (node (ref "P2") (pin "4") (pinfunction "4_4") (pintype "passive"))
      (node (ref "T3") (pin "0") (pintype "passive"))
      (node (ref "T6") (pin "0") (pintype "passive"))
      (node (ref "U10") (pin "11") (pinfunction "V-_11") (pintype "passive"))
      (node (ref "U3") (pin "3") (pinfunction "GND_3") (pintype "passive"))
      (node (ref "U3") (pin "6") (pinfunction "GND_6") (pintype "passive"))
      (node (ref "U4") (pin "3") (pinfunction "GND_3") (pintype "passive"))
      (node (ref "U4") (pin "6") (pinfunction "GND_6") (pintype "passive"))
      (node (ref "U6") (pin "3") (pinfunction "COM_3") (pintype "passive"))
      (node (ref "U6") (pin "5") (pinfunction "COM_5") (pintype "passive"))
      (node (ref "U6") (pin "6") (pinfunction "COM_6") (pintype "passive"))
      (node (ref "U6") (pin "7") (pinfunction "COM_7") (pintype "passive"))
      (node (ref "U7") (pin "5") (pinfunction "V-_5") (pintype "passive"))
      (node (ref "U8") (pin "43") (pinfunction "AGND_43") (pintype "passive"))
      (node (ref "U8") (pin "54") (pinfunction "AGND_54") (pintype "passive"))
      (node (ref "U8") (pin "57") (pinfunction "VREFN_57") (pintype "passive"))
      (node (ref "U8") (pin "58") (pinfunction "AGND_58") (pintype "passive"))
      (node (ref "U8") (pin "59") (pinfunction "AGND_59") (pintype "passive"))
      (node (ref "U8") (pin "6") (pinfunction "AGND_6") (pintype "passive"))
      (node (ref "U9") (pin "5") (pinfunction "V-_5") (pintype "passive"))
    )
    (net (code "69") (name "DGND") (class "Default")
      (node (ref "C26") (pin "2") (pinfunction "2_2") (pintype "passive"))
      (node (ref "C30") (pin "2") (pinfunction "2_2") (pintype "passive"))
      (node (ref "C53") (pin "1") (pinfunction "1_1") (pintype "passive"))
      (node (ref "C58") (pin "2") (pinfunction "2_2") (pintype "passive"))
      (node (ref "C59") (pin "2") (pinfunction "2_2") (pintype "passive"))
      (node (ref "C61") (pin "2") (pinfunction "2_2") (pintype "passive"))
      (node (ref "C63") (pin "2") (pinfunction "2_2") (pintype "passive"))
      (node (ref "NT1") (pin "1") (pintype "passive"))
      (node (ref "P3") (pin "15") (pinfunction "15_15") (pintype "passive"))
      (node (ref "P4") (pin "16") (pinfunction "16_16") (pintype "passive"))
      (node (ref "T4") (pin "0") (pintype "passive"))
      (node (ref "U5") (pin "2") (pinfunction "GND_2") (pintype "passive"))
      (node (ref "U8") (pin "10") (pinfunction "CLKDIV_10") (pintype "passive"))
      (node (ref "U8") (pin "21") (pinfunction "DGND_21") (pintype "passive"))
      (node (ref "U8") (pin "24") (pinfunction "DGND_24") (pintype "passive"))
      (node (ref "U8") (pin "25") (pinfunction "DGND_25") (pintype "passive"))
      (node (ref "U8") (pin "30") (pinfunction "FORMAT2_30") (pintype "passive"))
      (node (ref "U8") (pin "31") (pinfunction "FORMAT1_31") (pintype "passive"))
      (node (ref "U8") (pin "7") (pinfunction "DGND_7") (pintype "passive"))
      (node (ref "U8") (pin "8") (pinfunction "TEST0_8") (pintype "passive"))
      (node (ref "U8") (pin "9") (pinfunction "TEST1_9") (pintype "passive"))
      (node (ref "Y1") (pin "2") (pinfunction "GND_2") (pintype "passive"))
    )
    (net (code "70") (name "Net-(C41-Pad1)") (class "Default")
      (node (ref "C41") (pin "1") (pinfunction "1_1") (pintype "passive"))
      (node (ref "C42") (pin "1") (pinfunction "1_1") (pintype "passive"))
      (node (ref "R34") (pin "2") (pinfunction "2_2") (pintype "passive"))
      (node (ref "R35") (pin "1") (pinfunction "1_1") (pintype "passive"))
    )
    (net (code "71") (name "Net-(D1-Cathode)") (class "Default")
      (node (ref "D1") (pin "1") (pinfunction "Cathode_1") (pintype "passive"))
      (node (ref "R31") (pin "1") (pinfunction "1_1") (pintype "passive"))
      (node (ref "R34") (pin "1") (pinfunction "1_1") (pintype "passive"))
    )
    (net (code "72") (name "Net-(D2-K)") (class "Default")
      (node (ref "C30") (pin "1") (pinfunction "1_1") (pintype "passive"))
      (node (ref "C31") (pin "1") (pinfunction "1_1") (pintype "passive"))
      (node (ref "D2") (pin "2") (pinfunction "K_2") (pintype "passive"))
      (node (ref "T8") (pin "0") (pintype "passive"))
      (node (ref "U3") (pin "2") (pinfunction "IN_2") (pintype "passive"))
      (node (ref "U5") (pin "1") (pinfunction "IN_1") (pintype "passive"))
    )
    (net (code "73") (name "Net-(D3-K)") (class "Default")
      (node (ref "C32") (pin "1") (pinfunction "1_1") (pintype "passive"))
      (node (ref "D3") (pin "2") (pinfunction "K_2") (pintype "passive"))
      (node (ref "T7") (pin "0") (pintype "passive"))
      (node (ref "U4") (pin "2") (pinfunction "IN_2") (pintype "passive"))
    )
    (net (code "74") (name "Net-(P3-Pad2)") (class "Default")
      (node (ref "P3") (pin "2") (pinfunction "2_2") (pintype "passive"))
      (node (ref "P4") (pin "1") (pinfunction "1_1") (pintype "passive"))
    )
    (net (code "75") (name "Net-(P3-Pad4)") (class "Default")
      (node (ref "P3") (pin "4") (pinfunction "4_4") (pintype "passive"))
      (node (ref "P4") (pin "3") (pinfunction "3_3") (pintype "passive"))
    )
    (net (code "76") (name "Net-(P3-Pad6)") (class "Default")
      (node (ref "P3") (pin "6") (pinfunction "6_6") (pintype "passive"))
      (node (ref "P4") (pin "5") (pinfunction "5_5") (pintype "passive"))
    )
    (net (code "77") (name "Net-(P3-Pad8)") (class "Default")
      (node (ref "P3") (pin "8") (pinfunction "8_8") (pintype "passive"))
      (node (ref "P4") (pin "7") (pinfunction "7_7") (pintype "passive"))
    )
    (net (code "78") (name "Net-(P3-Pad10)") (class "Default")
      (node (ref "P3") (pin "10") (pinfunction "10_10") (pintype "passive"))
      (node (ref "P4") (pin "9") (pinfunction "9_9") (pintype "passive"))
    )
    (net (code "79") (name "Net-(P3-Pad12)") (class "Default")
      (node (ref "P3") (pin "12") (pinfunction "12_12") (pintype "passive"))
      (node (ref "P4") (pin "11") (pinfunction "11_11") (pintype "passive"))
    )
    (net (code "80") (name "Net-(P3-Pad14)") (class "Default")
      (node (ref "P3") (pin "14") (pinfunction "14_14") (pintype "passive"))
      (node (ref "P4") (pin "13") (pinfunction "13_13") (pintype "passive"))
    )
    (net (code "81") (name "Net-(P3-Pad16)") (class "Default")
      (node (ref "P3") (pin "16") (pinfunction "16_16") (pintype "passive"))
      (node (ref "P4") (pin "15") (pinfunction "15_15") (pintype "passive"))
    )
    (net (code "82") (name "Net-(U3-PG)") (class "Default")
      (node (ref "R28") (pin "2") (pinfunction "2_2") (pintype "passive"))
      (node (ref "T9") (pin "0") (pintype "passive"))
      (node (ref "U3") (pin "5") (pinfunction "PG_5") (pintype "passive"))
      (node (ref "U4") (pin "1") (pinfunction "~{SHDN}_1") (pintype "passive"))
    )
    (net (code "83") (name "Net-(U3-~{SHDN})") (class "Default")
      (node (ref "C27") (pin "1") (pinfunction "1_1") (pintype "passive"))
      (node (ref "R27") (pin "2") (pinfunction "2_2") (pintype "passive"))
      (node (ref "T10") (pin "0") (pintype "passive"))
      (node (ref "U3") (pin "1") (pinfunction "~{SHDN}_1") (pintype "passive"))
    )
    (net (code "84") (name "Net-(U6-ST)") (class "Default")
      (node (ref "R29") (pin "2") (pinfunction "2_2") (pintype "passive"))
      (node (ref "U6") (pin "2") (pinfunction "ST_2") (pintype "passive"))
    )
    (net (code "85") (name "Net-(U7-+IN)") (class "Default")
      (node (ref "R35") (pin "2") (pinfunction "2_2") (pintype "passive"))
      (node (ref "T18") (pin "0") (pintype "passive"))
      (node (ref "U7") (pin "3") (pinfunction "+IN_3") (pintype "passive"))
    )
    (net (code "86") (name "Net-(U7--IN)") (class "Default")
      (node (ref "C37") (pin "1") (pinfunction "1_1") (pintype "passive"))
      (node (ref "R30") (pin "1") (pinfunction "1_1") (pintype "passive"))
      (node (ref "U7") (pin "4") (pinfunction "-IN_4") (pintype "passive"))
    )
    (net (code "87") (name "Net-(U7-Out)") (class "Default")
      (node (ref "C37") (pin "2") (pinfunction "2_2") (pintype "passive"))
      (node (ref "R32") (pin "1") (pinfunction "1_1") (pintype "passive"))
      (node (ref "U7") (pin "1") (pinfunction "Out_1") (pintype "passive"))
    )
    (net (code "88") (name "Net-(U8-CLK)") (class "Default")
      (node (ref "U8") (pin "27") (pinfunction "CLK_27") (pintype "passive"))
      (node (ref "Y1") (pin "3") (pinfunction "OUT_3") (pintype "passive"))
    )
    (net (code "89") (name "Net-(U8-DOUT1)") (class "Default")
      (node (ref "R44") (pin "1") (pinfunction "1_1") (pintype "passive"))
      (node (ref "U8") (pin "20") (pinfunction "DOUT1_20") (pintype "passive"))
    )
    (net (code "90") (name "Net-(U8-VCOM)") (class "Default")
      (node (ref "C44") (pin "1") (pinfunction "1_1") (pintype "passive"))
      (node (ref "U8") (pin "55") (pinfunction "VCOM_55") (pintype "passive"))
      (node (ref "U9") (pin "3") (pinfunction "+IN_3") (pintype "passive"))
    )
    (net (code "91") (name "Net-(U9--IN)") (class "Default")
      (node (ref "R43") (pin "1") (pinfunction "1_1") (pintype "passive"))
      (node (ref "U9") (pin "1") (pinfunction "Out_1") (pintype "passive"))
      (node (ref "U9") (pin "4") (pinfunction "-IN_4") (pintype "passive"))
    )
    (net (code "92") (name "Net-(U10A-+IN)") (class "Default")
      (node (ref "C36") (pin "2") (pinfunction "2_2") (pintype "passive"))
      (node (ref "T12") (pin "0") (pintype "passive"))
      (node (ref "U10") (pin "3") (pinfunction "+IN_3") (pintype "passive"))
      (node (ref "U6") (pin "12") (pinfunction "Xout_12") (pintype "passive"))
    )
    (net (code "93") (name "Net-(U10B-+IN)") (class "Default")
      (node (ref "C35") (pin "2") (pinfunction "2_2") (pintype "passive"))
      (node (ref "T13") (pin "0") (pintype "passive"))
      (node (ref "U10") (pin "5") (pinfunction "+IN_5") (pintype "passive"))
      (node (ref "U6") (pin "10") (pinfunction "Yout_10") (pintype "passive"))
    )
    (net (code "94") (name "Net-(U10C-+IN)") (class "Default")
      (node (ref "C34") (pin "2") (pinfunction "2_2") (pintype "passive"))
      (node (ref "T14") (pin "0") (pintype "passive"))
      (node (ref "U10") (pin "10") (pinfunction "+IN_10") (pintype "passive"))
      (node (ref "U6") (pin "8") (pinfunction "Zout_8") (pintype "passive"))
    )
    (net (code "95") (name "Vbat") (class "Default")
      (node (ref "D2") (pin "1") (pinfunction "A_1") (pintype "passive"))
      (node (ref "D3") (pin "1") (pinfunction "A_1") (pintype "passive"))
      (node (ref "P3") (pin "13") (pinfunction "13_13") (pintype "passive"))
      (node (ref "P4") (pin "14") (pinfunction "14_14") (pintype "passive"))
    )
    (net (code "96") (name "unconnected-(D1-Trim-Pad3)") (class "Default")
      (node (ref "D1") (pin "3") (pinfunction "Trim_3") (pintype "passive"))
    )
    (net (code "97") (name "unconnected-(D4-Trim-Pad3)") (class "Default")
      (node (ref "D4") (pin "3") (pinfunction "Trim_3") (pintype "passive"))
    )
    (net (code "98") (name "unconnected-(D5-Trim-Pad3)") (class "Default")
      (node (ref "D5") (pin "3") (pinfunction "Trim_3") (pintype "passive"))
    )
    (net (code "99") (name "unconnected-(P1-Pad2)") (class "Default")
      (node (ref "P1") (pin "2") (pinfunction "2_2") (pintype "passive"))
    )
    (net (code "100") (name "unconnected-(P2-Pad2)") (class "Default")
      (node (ref "P2") (pin "2") (pinfunction "2_2") (pintype "passive"))
    )
    (net (code "101") (name "unconnected-(P3-Pad11)") (class "Default")
      (node (ref "P3") (pin "11") (pinfunction "11_11") (pintype "passive"))
    )
    (net (code "102") (name "unconnected-(P4-Pad10)") (class "Default")
      (node (ref "P4") (pin "10") (pinfunction "10_10") (pintype "passive"))
    )
    (net (code "103") (name "unconnected-(P4-Pad12)") (class "Default")
      (node (ref "P4") (pin "12") (pinfunction "12_12") (pintype "passive"))
    )
    (net (code "104") (name "unconnected-(U4-PG-Pad5)") (class "Default")
      (node (ref "U4") (pin "5") (pinfunction "PG_5") (pintype "passive"))
    )
    (net (code "105") (name "unconnected-(U5-NC-Pad3)") (class "Default")
      (node (ref "U5") (pin "3") (pinfunction "NC_3") (pintype "passive"))
    )
    (net (code "106") (name "unconnected-(U6-NC-Pad1)") (class "Default")
      (node (ref "U6") (pin "1") (pinfunction "NC_1") (pintype "passive"))
    )
    (net (code "107") (name "unconnected-(U6-NC-Pad4)") (class "Default")
      (node (ref "U6") (pin "4") (pinfunction "NC_4") (pintype "passive"))
    )
    (net (code "108") (name "unconnected-(U6-NC-Pad9)") (class "Default")
      (node (ref "U6") (pin "9") (pinfunction "NC_9") (pintype "passive"))
    )
    (net (code "109") (name "unconnected-(U6-NC-Pad11)") (class "Default")
      (node (ref "U6") (pin "11") (pinfunction "NC_11") (pintype "passive"))
    )
    (net (code "110") (name "unconnected-(U6-NC-Pad13)") (class "Default")
      (node (ref "U6") (pin "13") (pinfunction "NC_13") (pintype "passive"))
    )
    (net (code "111") (name "unconnected-(U6-NC-Pad16)") (class "Default")
      (node (ref "U6") (pin "16") (pinfunction "NC_16") (pintype "passive"))
    )
    (net (code "112") (name "unconnected-(U8-DIN-Pad12)") (class "Default")
      (node (ref "U8") (pin "12") (pinfunction "DIN_12") (pintype "passive"))
    )
    (net (code "113") (name "unconnected-(U8-DOUT2-Pad19)") (class "Default")
      (node (ref "U8") (pin "19") (pinfunction "DOUT2_19") (pintype "passive"))
    )
    (net (code "114") (name "unconnected-(U8-DOUT3-Pad18)") (class "Default")
      (node (ref "U8") (pin "18") (pinfunction "DOUT3_18") (pintype "passive"))
    )
    (net (code "115") (name "unconnected-(U8-DOUT4-Pad17)") (class "Default")
      (node (ref "U8") (pin "17") (pinfunction "DOUT4_17") (pintype "passive"))
    )
    (net (code "116") (name "unconnected-(U8-DOUT5-Pad16)") (class "Default")
      (node (ref "U8") (pin "16") (pinfunction "DOUT5_16") (pintype "passive"))
    )
    (net (code "117") (name "unconnected-(U8-DOUT6-Pad15)") (class "Default")
      (node (ref "U8") (pin "15") (pinfunction "DOUT6_15") (pintype "passive"))
    )
    (net (code "118") (name "unconnected-(U8-DOUT7-Pad14)") (class "Default")
      (node (ref "U8") (pin "14") (pinfunction "DOUT7_14") (pintype "passive"))
    )
    (net (code "119") (name "unconnected-(U8-DOUT8-Pad13)") (class "Default")
      (node (ref "U8") (pin "13") (pinfunction "DOUT8_13") (pintype "passive"))
    )
    (net (code "120") (name "unconnected-(U8-NC-Pad33)") (class "Default")
      (node (ref "U8") (pin "33") (pinfunction "NC_33") (pintype "passive"))
    )
  )
)
